# MCU.net
KiCad netlist of a schematic drawn in Altium Designer
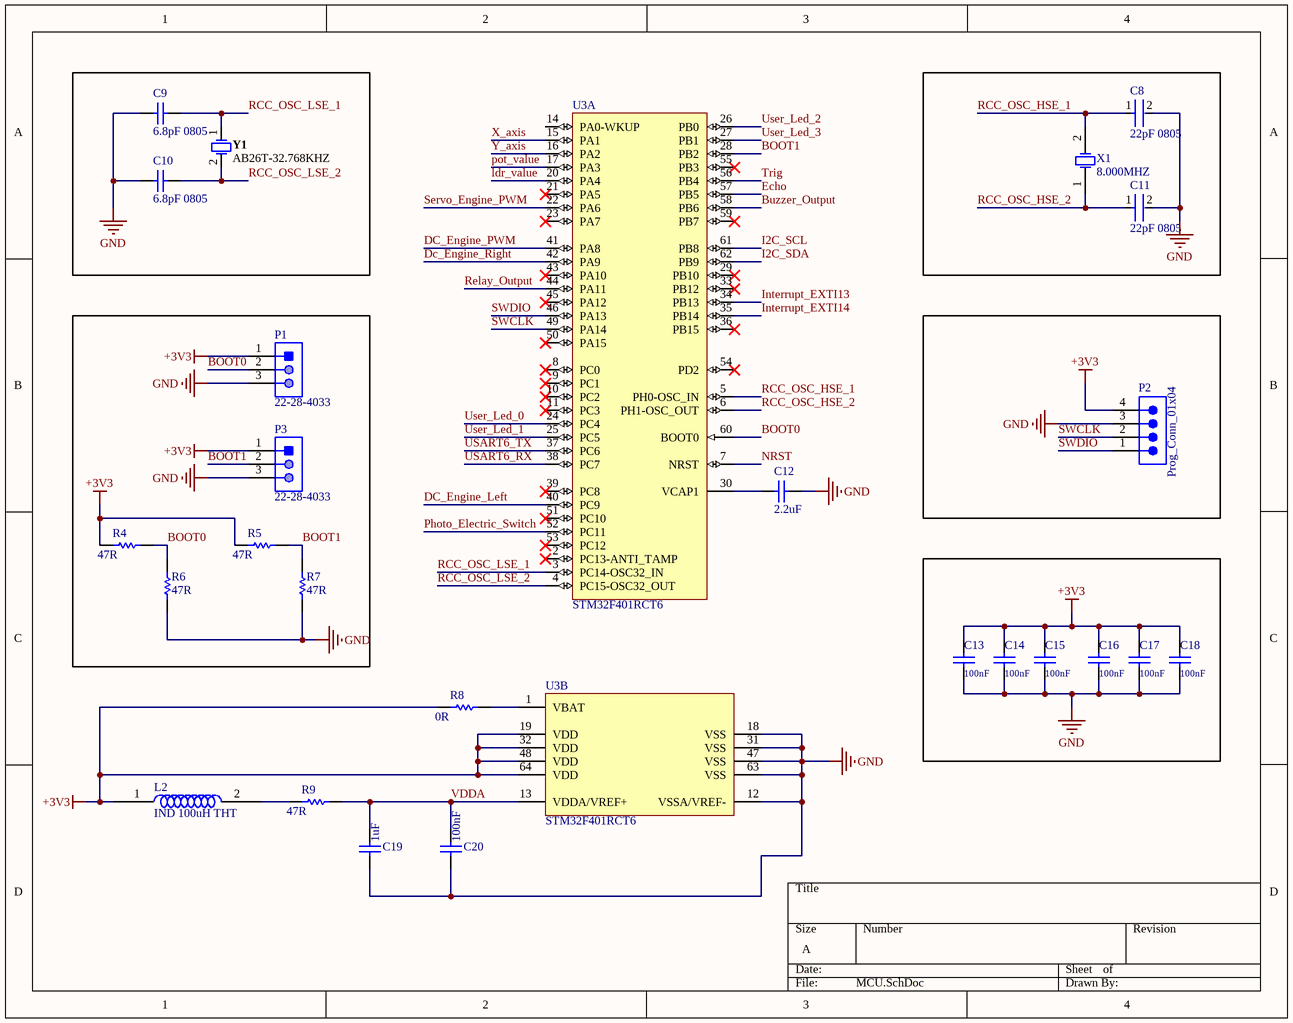
[diagram p0: MCU.SchDoc]

(export (version "E")
  (design (tool "Eeschema 10.0.6"))
  (components
    (comp (ref "C8")
      (value "22pF 0805")
      (footprint "FP-C0805C-DN-MFG")
      (description "CAP CER 22PF 50V 10% NP0 0805")
      (fields (field (name "MANUFACTURER PART NUMBER") "C0805C220K5GACTU") (field (name "TOLERANCE") "0.1"))
      (libsource (lib "Altium Content Vault") (part "b4654b650e69147ec39a6b967a45e02"))
    )
    (comp (ref "C9")
      (value "6.8pF 0805")
      (footprint "CAPC0805(2012)75_N")
      (description "CAP 6.8pF 25V ±0.25pF 0805 (2012 Metric) Thickness 0.75mm SMD")
      (fields (field (name "TOLERANCE") "Â±0.25pF"))
      (libsource (lib "Altium Content Vault") (part "CAP"))
    )
    (comp (ref "C10")
      (value "6.8pF 0805")
      (footprint "CAPC0805(2012)75_N")
      (description "CAP 6.8pF 25V ±0.25pF 0805 (2012 Metric) Thickness 0.75mm SMD")
      (fields (field (name "TOLERANCE") "Â±0.25pF"))
      (libsource (lib "Altium Content Vault") (part "CAP"))
    )
    (comp (ref "C11")
      (value "22pF 0805")
      (footprint "FP-C0805C-DN-MFG")
      (description "CAP CER 22PF 50V 10% NP0 0805")
      (fields (field (name "MANUFACTURER PART NUMBER") "C0805C220K5GACTU") (field (name "TOLERANCE") "0.1"))
      (libsource (lib "Altium Content Vault") (part "b4654b650e69147ec39a6b967a45e02"))
    )
    (comp (ref "C12")
      (value "2.2uF")
      (footprint "CAPC2013X135X45LL10T25")
      (fields (field (name "MANUFACTURER") "Murata") (field (name "PART NUMBER") "GRM21BR71H105KA12L"))
      (libsource (lib "Altium Content Vault") (part "CAP"))
    )
    (comp (ref "C13")
      (value "100nF")
      (footprint "CAPC2013X135X45LL10T25")
      (fields (field (name "MANUFACTURER") "Murata") (field (name "PART NUMBER") "GRM21BR71H105KA12L"))
      (libsource (lib "Altium Content Vault") (part "CAP"))
    )
    (comp (ref "C14")
      (value "100nF")
      (footprint "CAPC2013X135X45LL10T25")
      (fields (field (name "MANUFACTURER") "Murata") (field (name "PART NUMBER") "GRM21BR71H105KA12L"))
      (libsource (lib "Altium Content Vault") (part "CAP"))
    )
    (comp (ref "C15")
      (value "100nF")
      (footprint "CAPC2013X135X45LL10T25")
      (fields (field (name "MANUFACTURER") "Murata") (field (name "PART NUMBER") "GRM21BR71H105KA12L"))
      (libsource (lib "Altium Content Vault") (part "CAP"))
    )
    (comp (ref "C16")
      (value "100nF")
      (footprint "CAPC2013X135X45LL10T25")
      (fields (field (name "MANUFACTURER") "Murata") (field (name "PART NUMBER") "GRM21BR71H105KA12L"))
      (libsource (lib "Altium Content Vault") (part "CAP"))
    )
    (comp (ref "C17")
      (value "100nF")
      (footprint "CAPC2013X135X45LL10T25")
      (fields (field (name "MANUFACTURER") "Murata") (field (name "PART NUMBER") "GRM21BR71H105KA12L"))
      (libsource (lib "Altium Content Vault") (part "CAP"))
    )
    (comp (ref "C18")
      (value "100nF")
      (footprint "CAPC2013X135X45LL10T25")
      (fields (field (name "MANUFACTURER") "Murata") (field (name "PART NUMBER") "GRM21BR71H105KA12L"))
      (libsource (lib "Altium Content Vault") (part "CAP"))
    )
    (comp (ref "C19")
      (value "1uF")
      (footprint "CAPC2013X135X45LL10T25")
      (fields (field (name "MANUFACTURER") "Murata") (field (name "PART NUMBER") "GRM21BR71H105KA12L"))
      (libsource (lib "Altium Content Vault") (part "CAP"))
    )
    (comp (ref "C20")
      (value "100nF")
      (footprint "CAPC2013X135X45LL10T25")
      (fields (field (name "MANUFACTURER") "Murata") (field (name "PART NUMBER") "GRM21BR71H105KA12L"))
      (libsource (lib "Altium Content Vault") (part "CAP"))
    )
    (comp (ref "L2")
      (value "IND 100uH THT")
      (footprint "INDUCTOR THT")
      (description "Fixed Ind 100uH THT")
      (libsource (lib "User_Library") (part "IND 100uH THT"))
    )
    (comp (ref "P1")
      (value "22-28-4033")
      (footprint "MOLX-22-28-4033_V")
      (description "Male Header, Pitch 2.54 mm, 1 x 3 Position, Height 8.38 mm, Tail Length 3.18 mm, RoHS, Bulk")
      (fields (field (name "MANUFACTURER") "Molex"))
      (libsource (lib "Altium Content Vault") (part "CN-1P-M-R3"))
    )
    (comp (ref "P2")
      (value "Prog_Conn_01x04")
      (footprint "SMTC-TSW-104-08-X-S")
      (description "0.025\" SQ Post Header, Through-hole, Vertical, -55 to 105 degC, 2.54 mm Pitch, 4-Pin, Male, RoHS")
      (fields (field (name "PARTNUMBER") "TSW-104-08-T-S") (field (name "MANUFACTURER") "Samtec"))
      (libsource (lib "Altium Content Vault") (part "SMTC-TSW-104-08-X-S"))
    )
    (comp (ref "P3")
      (value "22-28-4033")
      (footprint "MOLX-22-28-4033_V")
      (description "Male Header, Pitch 2.54 mm, 1 x 3 Position, Height 8.38 mm, Tail Length 3.18 mm, RoHS, Bulk")
      (fields (field (name "MANUFACTURER") "Molex"))
      (libsource (lib "Altium Content Vault") (part "CN-1P-M-R3"))
    )
    (comp (ref "R4")
      (value "47R")
      (footprint "RESC2013X70X40NL20T20")
      (fields (field (name "PART NUMBER") "ERJ6ENF47R0V") (field (name "MANUFACTURER") "Panasonic"))
      (libsource (lib "Altium Content Vault") (part "RES"))
    )
    (comp (ref "R5")
      (value "47R")
      (footprint "RESC2013X70X40NL20T20")
      (fields (field (name "PART NUMBER") "ERJ6ENF47R0V") (field (name "MANUFACTURER") "Panasonic"))
      (libsource (lib "Altium Content Vault") (part "RES"))
    )
    (comp (ref "R6")
      (value "47R")
      (footprint "RESC2013X70X40NL20T20")
      (fields (field (name "PART NUMBER") "ERJ6ENF47R0V") (field (name "MANUFACTURER") "Panasonic"))
      (libsource (lib "Altium Content Vault") (part "RES"))
    )
    (comp (ref "R7")
      (value "47R")
      (footprint "RESC2013X70X40NL20T20")
      (fields (field (name "PART NUMBER") "ERJ6ENF47R0V") (field (name "MANUFACTURER") "Panasonic"))
      (libsource (lib "Altium Content Vault") (part "RES"))
    )
    (comp (ref "R8")
      (value "0R")
      (footprint "RESC2013X70X40NL20T20")
      (fields (field (name "PART NUMBER") "ERJ6ENF47R0V") (field (name "MANUFACTURER") "Panasonic"))
      (libsource (lib "Altium Content Vault") (part "RES"))
    )
    (comp (ref "R9")
      (value "47R")
      (footprint "RESC2013X70X40NL20T20")
      (fields (field (name "PART NUMBER") "ERJ6ENF47R0V") (field (name "MANUFACTURER") "Panasonic"))
      (libsource (lib "Altium Content Vault") (part "RES"))
    )
    (comp (ref "U3")
      (value "STM32F401RCT6")
      (footprint "STM-LQFP64_N")
      (fields (field (name "MANUFACTURER") "STMicroelectronics"))
      (libsource (lib "Altium Content Vault") (part "MC-ARM-STM32F401-SQ64"))
    )
    (comp (ref "X1")
      (value "8.000MHZ")
      (footprint "ABRA-ABLS-14.7456MHZ-B2-T_V")
      (description "Low Profile Crystal, 8.0 MHz, +/- 30 ppm, -20 to 70 degC, 2-Pin SMD, RoHS, Tape and Reel")
      (fields (field (name "MANUFACTURER") "ABRACON") (field (name "TOLERANCE") "30PPM"))
      (libsource (lib "Altium Content Vault") (part "XTAL_1-2-2"))
    )
    (comp (ref "Y1")
      (value "AB26T-32.768KHZ")
      (footprint "ABRA-AB26T")
      (description "Crystal, 12.5 pF, 32.768 KHz, -10 to 60 degC, 2-Pin THD, RoHS, Bulk")
      (fields (field (name "MANUFACTURER") "ABRACON") (field (name "TOLERANCE") "20PPM"))
      (libsource (lib "Altium Content Vault") (part "XTAL-1-2-2"))
    )
  )
  (nets
    (net (code "1") (name "+3V3") (class "Default")
      (node (ref "C13") (pin "2") (pinfunction "2_2") (pintype "passive"))
      (node (ref "C14") (pin "2") (pinfunction "2_2") (pintype "passive"))
      (node (ref "C15") (pin "2") (pinfunction "2_2") (pintype "passive"))
      (node (ref "C16") (pin "2") (pinfunction "2_2") (pintype "passive"))
      (node (ref "C17") (pin "2") (pinfunction "2_2") (pintype "passive"))
      (node (ref "C18") (pin "2") (pinfunction "2_2") (pintype "passive"))
      (node (ref "L2") (pin "1") (pinfunction "1_1") (pintype "power_in"))
      (node (ref "P1") (pin "1") (pinfunction "1_1") (pintype "passive"))
      (node (ref "P2") (pin "4") (pinfunction "4_4") (pintype "passive"))
      (node (ref "P3") (pin "1") (pinfunction "1_1") (pintype "passive"))
      (node (ref "R4") (pin "1") (pinfunction "1_1") (pintype "passive"))
      (node (ref "R5") (pin "1") (pinfunction "1_1") (pintype "passive"))
      (node (ref "R8") (pin "1") (pinfunction "1_1") (pintype "passive"))
      (node (ref "U3") (pin "19") (pinfunction "VDD_19") (pintype "power_in"))
      (node (ref "U3") (pin "32") (pinfunction "VDD_32") (pintype "power_in"))
      (node (ref "U3") (pin "48") (pinfunction "VDD_48") (pintype "power_in"))
      (node (ref "U3") (pin "64") (pinfunction "VDD_64") (pintype "power_in"))
    )
    (net (code "2") (name "/BOOT0") (class "Default")
      (node (ref "P1") (pin "2") (pinfunction "2_2") (pintype "passive"))
      (node (ref "R4") (pin "2") (pinfunction "2_2") (pintype "passive"))
      (node (ref "R6") (pin "2") (pinfunction "2_2") (pintype "passive"))
      (node (ref "U3") (pin "60") (pinfunction "BOOT0_60") (pintype "input"))
    )
    (net (code "3") (name "/BOOT1") (class "Default")
      (node (ref "P3") (pin "2") (pinfunction "2_2") (pintype "passive"))
      (node (ref "R5") (pin "2") (pinfunction "2_2") (pintype "passive"))
      (node (ref "R7") (pin "2") (pinfunction "2_2") (pintype "passive"))
      (node (ref "U3") (pin "28") (pinfunction "PB2_28") (pintype "bidirectional"))
    )
    (net (code "4") (name "/Buzzer_Output") (class "Default")
      (node (ref "U3") (pin "58") (pinfunction "PB6_58") (pintype "bidirectional"))
    )
    (net (code "5") (name "/DC_Engine_Left") (class "Default")
      (node (ref "U3") (pin "40") (pinfunction "PC9_40") (pintype "bidirectional"))
    )
    (net (code "6") (name "/DC_Engine_PWM") (class "Default")
      (node (ref "U3") (pin "41") (pinfunction "PA8_41") (pintype "bidirectional"))
    )
    (net (code "7") (name "/Dc_Engine_Right") (class "Default")
      (node (ref "U3") (pin "42") (pinfunction "PA9_42") (pintype "bidirectional"))
    )
    (net (code "8") (name "/Echo") (class "Default")
      (node (ref "U3") (pin "57") (pinfunction "PB5_57") (pintype "bidirectional"))
    )
    (net (code "9") (name "/I2C_SCL") (class "Default")
      (node (ref "U3") (pin "61") (pinfunction "PB8_61") (pintype "bidirectional"))
    )
    (net (code "10") (name "/I2C_SDA") (class "Default")
      (node (ref "U3") (pin "62") (pinfunction "PB9_62") (pintype "bidirectional"))
    )
    (net (code "11") (name "/Interrupt_EXTI13") (class "Default")
      (node (ref "U3") (pin "34") (pinfunction "PB13_34") (pintype "bidirectional"))
    )
    (net (code "12") (name "/Interrupt_EXTI14") (class "Default")
      (node (ref "U3") (pin "35") (pinfunction "PB14_35") (pintype "bidirectional"))
    )
    (net (code "13") (name "/NRST") (class "Default")
      (node (ref "U3") (pin "7") (pinfunction "NRST_7") (pintype "bidirectional"))
    )
    (net (code "14") (name "/Photo_Electric_Switch") (class "Default")
      (node (ref "U3") (pin "52") (pinfunction "PC11_52") (pintype "bidirectional"))
    )
    (net (code "15") (name "/RCC_OSC_HSE_1") (class "Default")
      (node (ref "C8") (pin "1") (pinfunction "1_1") (pintype "passive"))
      (node (ref "U3") (pin "5") (pinfunction "PH0-OSC_IN_5") (pintype "bidirectional"))
      (node (ref "X1") (pin "2") (pinfunction "X2_2") (pintype "passive"))
    )
    (net (code "16") (name "/RCC_OSC_HSE_2") (class "Default")
      (node (ref "C11") (pin "1") (pinfunction "1_1") (pintype "passive"))
      (node (ref "U3") (pin "6") (pinfunction "PH1-OSC_OUT_6") (pintype "bidirectional"))
      (node (ref "X1") (pin "1") (pinfunction "X1_1") (pintype "passive"))
    )
    (net (code "17") (name "/RCC_OSC_LSE_1") (class "Default")
      (node (ref "C9") (pin "2") (pinfunction "2_2") (pintype "passive"))
      (node (ref "U3") (pin "3") (pinfunction "PC14-OSC32_IN_3") (pintype "bidirectional"))
      (node (ref "Y1") (pin "1") (pinfunction "1_1") (pintype "passive"))
    )
    (net (code "18") (name "/RCC_OSC_LSE_2") (class "Default")
      (node (ref "C10") (pin "2") (pinfunction "2_2") (pintype "passive"))
      (node (ref "U3") (pin "4") (pinfunction "PC15-OSC32_OUT_4") (pintype "bidirectional"))
      (node (ref "Y1") (pin "2") (pinfunction "2_2") (pintype "passive"))
    )
    (net (code "19") (name "/Relay_Output") (class "Default")
      (node (ref "U3") (pin "44") (pinfunction "PA11_44") (pintype "bidirectional"))
    )
    (net (code "20") (name "/SWCLK") (class "Default")
      (node (ref "P2") (pin "2") (pinfunction "2_2") (pintype "passive"))
      (node (ref "U3") (pin "49") (pinfunction "PA14_49") (pintype "bidirectional"))
    )
    (net (code "21") (name "/SWDIO") (class "Default")
      (node (ref "P2") (pin "1") (pinfunction "1_1") (pintype "passive"))
      (node (ref "U3") (pin "46") (pinfunction "PA13_46") (pintype "bidirectional"))
    )
    (net (code "22") (name "/Servo_Engine_PWM") (class "Default")
      (node (ref "U3") (pin "22") (pinfunction "PA6_22") (pintype "bidirectional"))
    )
    (net (code "23") (name "/Trig") (class "Default")
      (node (ref "U3") (pin "56") (pinfunction "PB4_56") (pintype "bidirectional"))
    )
    (net (code "24") (name "/USART6_RX") (class "Default")
      (node (ref "U3") (pin "38") (pinfunction "PC7_38") (pintype "bidirectional"))
    )
    (net (code "25") (name "/USART6_TX") (class "Default")
      (node (ref "U3") (pin "37") (pinfunction "PC6_37") (pintype "bidirectional"))
    )
    (net (code "26") (name "/User_Led_0") (class "Default")
      (node (ref "U3") (pin "24") (pinfunction "PC4_24") (pintype "bidirectional"))
    )
    (net (code "27") (name "/User_Led_1") (class "Default")
      (node (ref "U3") (pin "25") (pinfunction "PC5_25") (pintype "bidirectional"))
    )
    (net (code "28") (name "/User_Led_2") (class "Default")
      (node (ref "U3") (pin "26") (pinfunction "PB0_26") (pintype "bidirectional"))
    )
    (net (code "29") (name "/User_Led_3") (class "Default")
      (node (ref "U3") (pin "27") (pinfunction "PB1_27") (pintype "bidirectional"))
    )
    (net (code "30") (name "/VDDA") (class "Default")
      (node (ref "C19") (pin "2") (pinfunction "2_2") (pintype "passive"))
      (node (ref "C20") (pin "2") (pinfunction "2_2") (pintype "passive"))
      (node (ref "R9") (pin "2") (pinfunction "2_2") (pintype "passive"))
      (node (ref "U3") (pin "13") (pinfunction "VDDA/VREF+_13") (pintype "power_in"))
    )
    (net (code "31") (name "/X_axis") (class "Default")
      (node (ref "U3") (pin "15") (pinfunction "PA1_15") (pintype "bidirectional"))
    )
    (net (code "32") (name "/Y_axis") (class "Default")
      (node (ref "U3") (pin "16") (pinfunction "PA2_16") (pintype "bidirectional"))
    )
    (net (code "33") (name "/ldr_value") (class "Default")
      (node (ref "U3") (pin "20") (pinfunction "PA4_20") (pintype "bidirectional"))
    )
    (net (code "34") (name "/pot_value") (class "Default")
      (node (ref "U3") (pin "17") (pinfunction "PA3_17") (pintype "bidirectional"))
    )
    (net (code "35") (name "GND") (class "Default")
      (node (ref "C10") (pin "1") (pinfunction "1_1") (pintype "passive"))
      (node (ref "C11") (pin "2") (pinfunction "2_2") (pintype "passive"))
      (node (ref "C12") (pin "1") (pinfunction "1_1") (pintype "passive"))
      (node (ref "C13") (pin "1") (pinfunction "1_1") (pintype "passive"))
      (node (ref "C14") (pin "1") (pinfunction "1_1") (pintype "passive"))
      (node (ref "C15") (pin "1") (pinfunction "1_1") (pintype "passive"))
      (node (ref "C16") (pin "1") (pinfunction "1_1") (pintype "passive"))
      (node (ref "C17") (pin "1") (pinfunction "1_1") (pintype "passive"))
      (node (ref "C18") (pin "1") (pinfunction "1_1") (pintype "passive"))
      (node (ref "C19") (pin "1") (pinfunction "1_1") (pintype "passive"))
      (node (ref "C20") (pin "1") (pinfunction "1_1") (pintype "passive"))
      (node (ref "C8") (pin "2") (pinfunction "2_2") (pintype "passive"))
      (node (ref "C9") (pin "1") (pinfunction "1_1") (pintype "passive"))
      (node (ref "P1") (pin "3") (pinfunction "3_3") (pintype "passive"))
      (node (ref "P2") (pin "3") (pinfunction "3_3") (pintype "passive"))
      (node (ref "P3") (pin "3") (pinfunction "3_3") (pintype "passive"))
      (node (ref "R6") (pin "1") (pinfunction "1_1") (pintype "passive"))
      (node (ref "R7") (pin "1") (pinfunction "1_1") (pintype "passive"))
      (node (ref "U3") (pin "12") (pinfunction "VSSA/VREF-_12") (pintype "power_in"))
      (node (ref "U3") (pin "18") (pinfunction "VSS_18") (pintype "power_in"))
      (node (ref "U3") (pin "31") (pinfunction "VSS_31") (pintype "power_in"))
      (node (ref "U3") (pin "47") (pinfunction "VSS_47") (pintype "power_in"))
      (node (ref "U3") (pin "63") (pinfunction "VSS_63") (pintype "power_in"))
    )
    (net (code "36") (name "Net-(L2-Pad2)") (class "Default")
      (node (ref "L2") (pin "2") (pinfunction "2_2") (pintype "power_in"))
      (node (ref "R9") (pin "1") (pinfunction "1_1") (pintype "passive"))
    )
    (net (code "37") (name "Net-(U3A-VCAP1)") (class "Default")
      (node (ref "C12") (pin "2") (pinfunction "2_2") (pintype "passive"))
      (node (ref "U3") (pin "30") (pinfunction "VCAP1_30") (pintype "power_in"))
    )
    (net (code "38") (name "Net-(U3B-VBAT)") (class "Default")
      (node (ref "R8") (pin "2") (pinfunction "2_2") (pintype "passive"))
      (node (ref "U3") (pin "1") (pinfunction "VBAT_1") (pintype "power_in"))
    )
    (net (code "39") (name "unconnected-(U3A-PA0-WKUP-Pad14)") (class "Default")
      (node (ref "U3") (pin "14") (pinfunction "PA0-WKUP_14") (pintype "bidirectional"))
    )
    (net (code "40") (name "unconnected-(U3A-PA5-Pad21)") (class "Default")
      (node (ref "U3") (pin "21") (pinfunction "PA5_21") (pintype "bidirectional+no_connect"))
    )
    (net (code "41") (name "unconnected-(U3A-PA7-Pad23)") (class "Default")
      (node (ref "U3") (pin "23") (pinfunction "PA7_23") (pintype "bidirectional+no_connect"))
    )
    (net (code "42") (name "unconnected-(U3A-PA10-Pad43)") (class "Default")
      (node (ref "U3") (pin "43") (pinfunction "PA10_43") (pintype "bidirectional+no_connect"))
    )
    (net (code "43") (name "unconnected-(U3A-PA12-Pad45)") (class "Default")
      (node (ref "U3") (pin "45") (pinfunction "PA12_45") (pintype "bidirectional+no_connect"))
    )
    (net (code "44") (name "unconnected-(U3A-PA15-Pad50)") (class "Default")
      (node (ref "U3") (pin "50") (pinfunction "PA15_50") (pintype "bidirectional+no_connect"))
    )
    (net (code "45") (name "unconnected-(U3A-PB3-Pad55)") (class "Default")
      (node (ref "U3") (pin "55") (pinfunction "PB3_55") (pintype "bidirectional+no_connect"))
    )
    (net (code "46") (name "unconnected-(U3A-PB7-Pad59)") (class "Default")
      (node (ref "U3") (pin "59") (pinfunction "PB7_59") (pintype "bidirectional+no_connect"))
    )
    (net (code "47") (name "unconnected-(U3A-PB10-Pad29)") (class "Default")
      (node (ref "U3") (pin "29") (pinfunction "PB10_29") (pintype "bidirectional+no_connect"))
    )
    (net (code "48") (name "unconnected-(U3A-PB12-Pad33)") (class "Default")
      (node (ref "U3") (pin "33") (pinfunction "PB12_33") (pintype "bidirectional+no_connect"))
    )
    (net (code "49") (name "unconnected-(U3A-PB15-Pad36)") (class "Default")
      (node (ref "U3") (pin "36") (pinfunction "PB15_36") (pintype "bidirectional+no_connect"))
    )
    (net (code "50") (name "unconnected-(U3A-PC0-Pad8)") (class "Default")
      (node (ref "U3") (pin "8") (pinfunction "PC0_8") (pintype "bidirectional+no_connect"))
    )
    (net (code "51") (name "unconnected-(U3A-PC1-Pad9)") (class "Default")
      (node (ref "U3") (pin "9") (pinfunction "PC1_9") (pintype "bidirectional+no_connect"))
    )
    (net (code "52") (name "unconnected-(U3A-PC2-Pad10)") (class "Default")
      (node (ref "U3") (pin "10") (pinfunction "PC2_10") (pintype "bidirectional+no_connect"))
    )
    (net (code "53") (name "unconnected-(U3A-PC3-Pad11)") (class "Default")
      (node (ref "U3") (pin "11") (pinfunction "PC3_11") (pintype "bidirectional+no_connect"))
    )
    (net (code "54") (name "unconnected-(U3A-PC8-Pad39)") (class "Default")
      (node (ref "U3") (pin "39") (pinfunction "PC8_39") (pintype "bidirectional+no_connect"))
    )
    (net (code "55") (name "unconnected-(U3A-PC10-Pad51)") (class "Default")
      (node (ref "U3") (pin "51") (pinfunction "PC10_51") (pintype "bidirectional+no_connect"))
    )
    (net (code "56") (name "unconnected-(U3A-PC12-Pad53)") (class "Default")
      (node (ref "U3") (pin "53") (pinfunction "PC12_53") (pintype "bidirectional+no_connect"))
    )
    (net (code "57") (name "unconnected-(U3A-PC13-ANTI_TAMP-Pad2)") (class "Default")
      (node (ref "U3") (pin "2") (pinfunction "PC13-ANTI_TAMP_2") (pintype "bidirectional+no_connect"))
    )
    (net (code "58") (name "unconnected-(U3A-PD2-Pad54)") (class "Default")
      (node (ref "U3") (pin "54") (pinfunction "PD2_54") (pintype "bidirectional+no_connect"))
    )
  )
)
